# Relay_Driver.net
KiCad netlist of a schematic drawn in Altium Designer
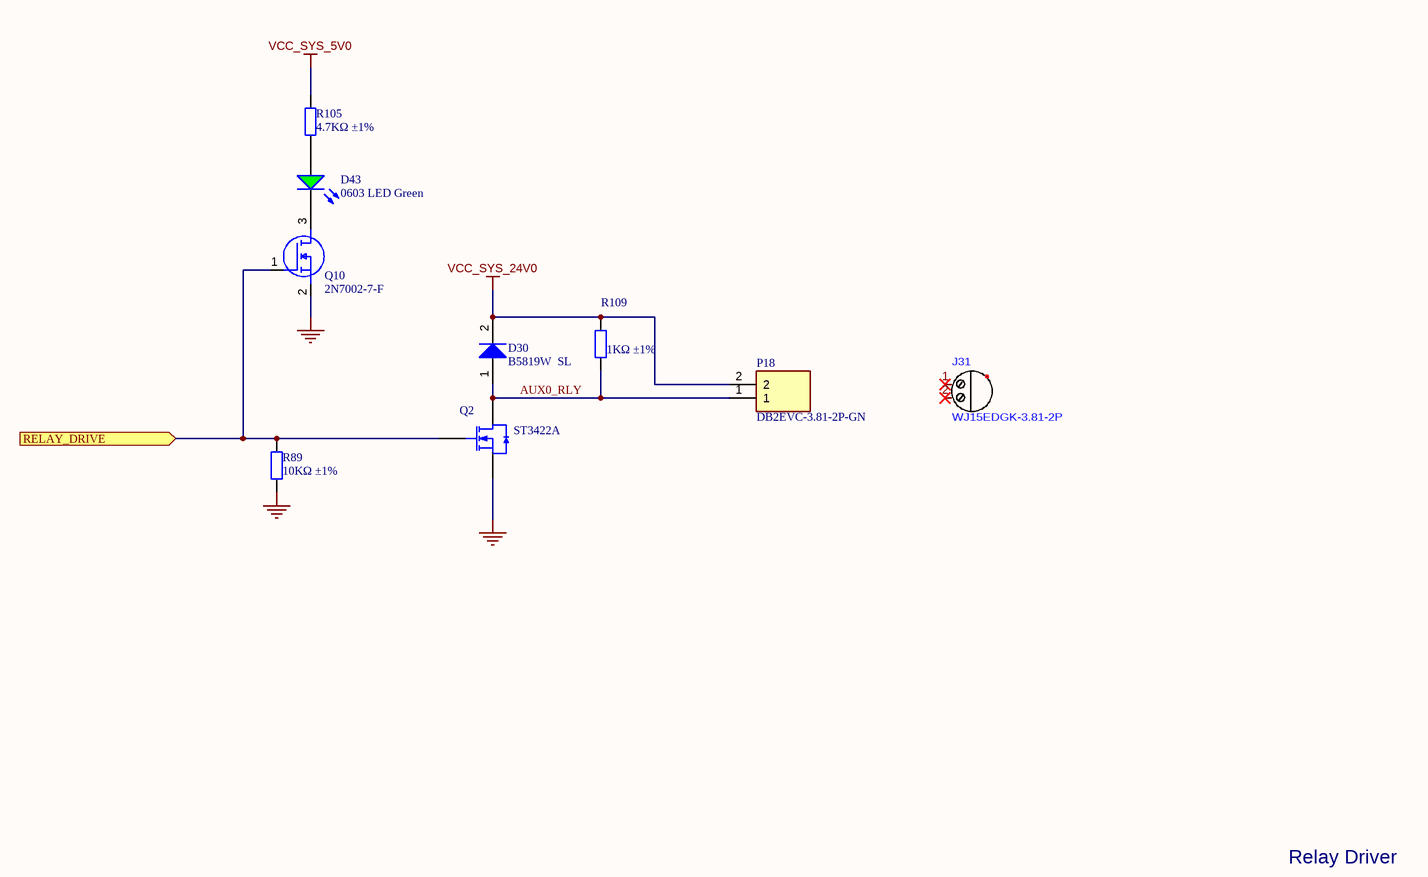
[diagram p0: Relay_Driver.SchDoc]

(export (version "E")
  (design (tool "Eeschema 10.0.6"))
  (components
    (comp (ref "D30")
      (value "B5819W  SL")
      (footprint "SOD-123")
      (description "Schottky Diode")
      (fields
        (field (name "MANUFACTURER PART NUMBER") "B5819W SL")
        (field (name "MANUFACTURER") "Jiangsu Changjing Electronics Technology")
      )
      (libsource (lib "Diode") (part "SOD-123 B5819W  SL"))
    )
    (comp (ref "D43")
      (value "0603 LED Green")
      (footprint "0603_LED_S1 - GREEN")
      (fields
        (field (name "MANUFACTURER PART NUMBER") "19-217/GHC-YR1S2/3T")
        (field (name "MANUFACTURER") "Everlight Elec")
      )
      (libsource (lib "Sienci_Labs") (part "19-217/GHC-YR1S2/3T"))
    )
    (comp (ref "J31")
      (value "WJ15EDGK-3.81-2P")
      (description "2 1 3.81mm Green Plug P=3.81mm Pluggable System Terminal Block ROHS")
      (fields (field (name "MANUFACTURER") "Ningbo"))
      (libsource (lib "Sienci_Labs") (part "WJ15EDGK-3.81-2P"))
    )
    (comp (ref "P18")
      (value "DB2EVC-3.81-2P-GN")
      (footprint "CONN-TH_5P-P3.81_DB2EVC-3.81-2p")
      (description "3.81mm Green Board Edge/Receptacle-Close Push-Pull,P=3.81mm Pluggable System Terminal Block ROHS")
      (fields (field (name "MANUFACTURER") "DIBO"))
      (libsource (lib "Sienci_Labs") (part "DB2EVC-3.81-2P-GN"))
    )
    (comp (ref "Q2")
      (value "ST3422A")
      (footprint "SOT-23-3L")
      (fields (field (name "MANUFACTURER") "STANSON Tech."))
      (libsource (lib "Sienci_Labs") (part "ST3422A"))
    )
    (comp (ref "Q10")
      (value "2N7002-7-F")
      (footprint "SOT-23(SOT-23-3)")
      (description "60V 115mA 7.5Ω@5V,50mA 370mW N Channel SOT-23 MOSFETs ROHS")
      (fields (field (name "MANUFACTURER") "Diodes Inc.") (field (name "MOUSER PART NUMBER") "621-2N7002-F"))
      (libsource (lib "Sienci_Labs") (part "2N7002-7-F"))
    )
    (comp (ref "R89")
      (value "10KΩ ±1%")
      (footprint "0402_R")
      (description "Chip resistor")
      (fields
        (field (name "MANUFACTURER") "Uniroyal Elec")
        (field (name "MANUFACTURER PART NUMBER") "0402WGF1002TCE")
      )
      (libsource (lib "RES") (part "0402 10K (1002) 1%"))
    )
    (comp (ref "R105")
      (value "4.7KΩ ±1%")
      (footprint "0402_R")
      (description "Chip resistor")
      (fields
        (field (name "MANUFACTURER") "Uniroyal Elec")
        (field (name "MANUFACTURER PART NUMBER") "0402WGF4701TCE")
      )
      (libsource (lib "RES") (part "0402 4.7K (4701) 1%"))
    )
    (comp (ref "R109")
      (value "1KΩ ±1%")
      (footprint "0603_R")
      (description "Chip resistor")
      (fields
        (field (name "MANUFACTURER") "Uniroyal Elec")
        (field (name "MANUFACTURER PART NUMBER") "0603WAF1001T5E")
      )
      (libsource (lib "RES") (part "0603 1K (1001) 1%"))
    )
  )
  (nets
    (net (code "1") (name "/AUX0_RLY") (class "Default")
      (node (ref "D30") (pin "1") (pinfunction "A_1") (pintype "passive"))
      (node (ref "P18") (pin "1") (pinfunction "1_1") (pintype "passive"))
      (node (ref "Q2") (pin "3") (pinfunction "D_3") (pintype "passive"))
      (node (ref "R109") (pin "1") (pinfunction "1_1") (pintype "passive"))
    )
    (net (code "2") (name "/RELAY_DRIVE") (class "Default")
      (node (ref "Q10") (pin "1") (pinfunction "G_1") (pintype "passive"))
      (node (ref "Q2") (pin "1") (pinfunction "G_1") (pintype "passive"))
      (node (ref "R89") (pin "2") (pinfunction "2_2") (pintype "passive"))
    )
    (net (code "3") (name "GND") (class "Default")
      (node (ref "Q10") (pin "2") (pinfunction "S_2") (pintype "passive"))
      (node (ref "Q2") (pin "2") (pinfunction "S_2") (pintype "passive"))
      (node (ref "R89") (pin "1") (pinfunction "1_1") (pintype "passive"))
    )
    (net (code "4") (name "Net-(D43-PadA)") (class "Default")
      (node (ref "D43") (pin "A") (pinfunction "A_A") (pintype "passive"))
      (node (ref "R105") (pin "1") (pinfunction "1_1") (pintype "passive"))
    )
    (net (code "5") (name "Net-(Q10-D)") (class "Default")
      (node (ref "D43") (pin "K") (pinfunction "K_K") (pintype "passive"))
      (node (ref "Q10") (pin "3") (pinfunction "D_3") (pintype "passive"))
    )
    (net (code "6") (name "VCC_SYS_5V0") (class "Default")
      (node (ref "R105") (pin "2") (pinfunction "2_2") (pintype "passive"))
    )
    (net (code "7") (name "VCC_SYS_24V0") (class "Default")
      (node (ref "D30") (pin "2") (pinfunction "K_2") (pintype "passive"))
      (node (ref "P18") (pin "2") (pinfunction "2_2") (pintype "passive"))
      (node (ref "R109") (pin "2") (pinfunction "2_2") (pintype "passive"))
    )
    (net (code "8") (name "unconnected-(J31-Pad1)") (class "Default")
      (node (ref "J31") (pin "1") (pinfunction "1_1") (pintype "passive+no_connect"))
    )
    (net (code "9") (name "unconnected-(J31-Pad2)") (class "Default")
      (node (ref "J31") (pin "2") (pinfunction "2_2") (pintype "passive+no_connect"))
    )
  )
)
